# Main.net
KiCad netlist of a schematic drawn in Altium Designer
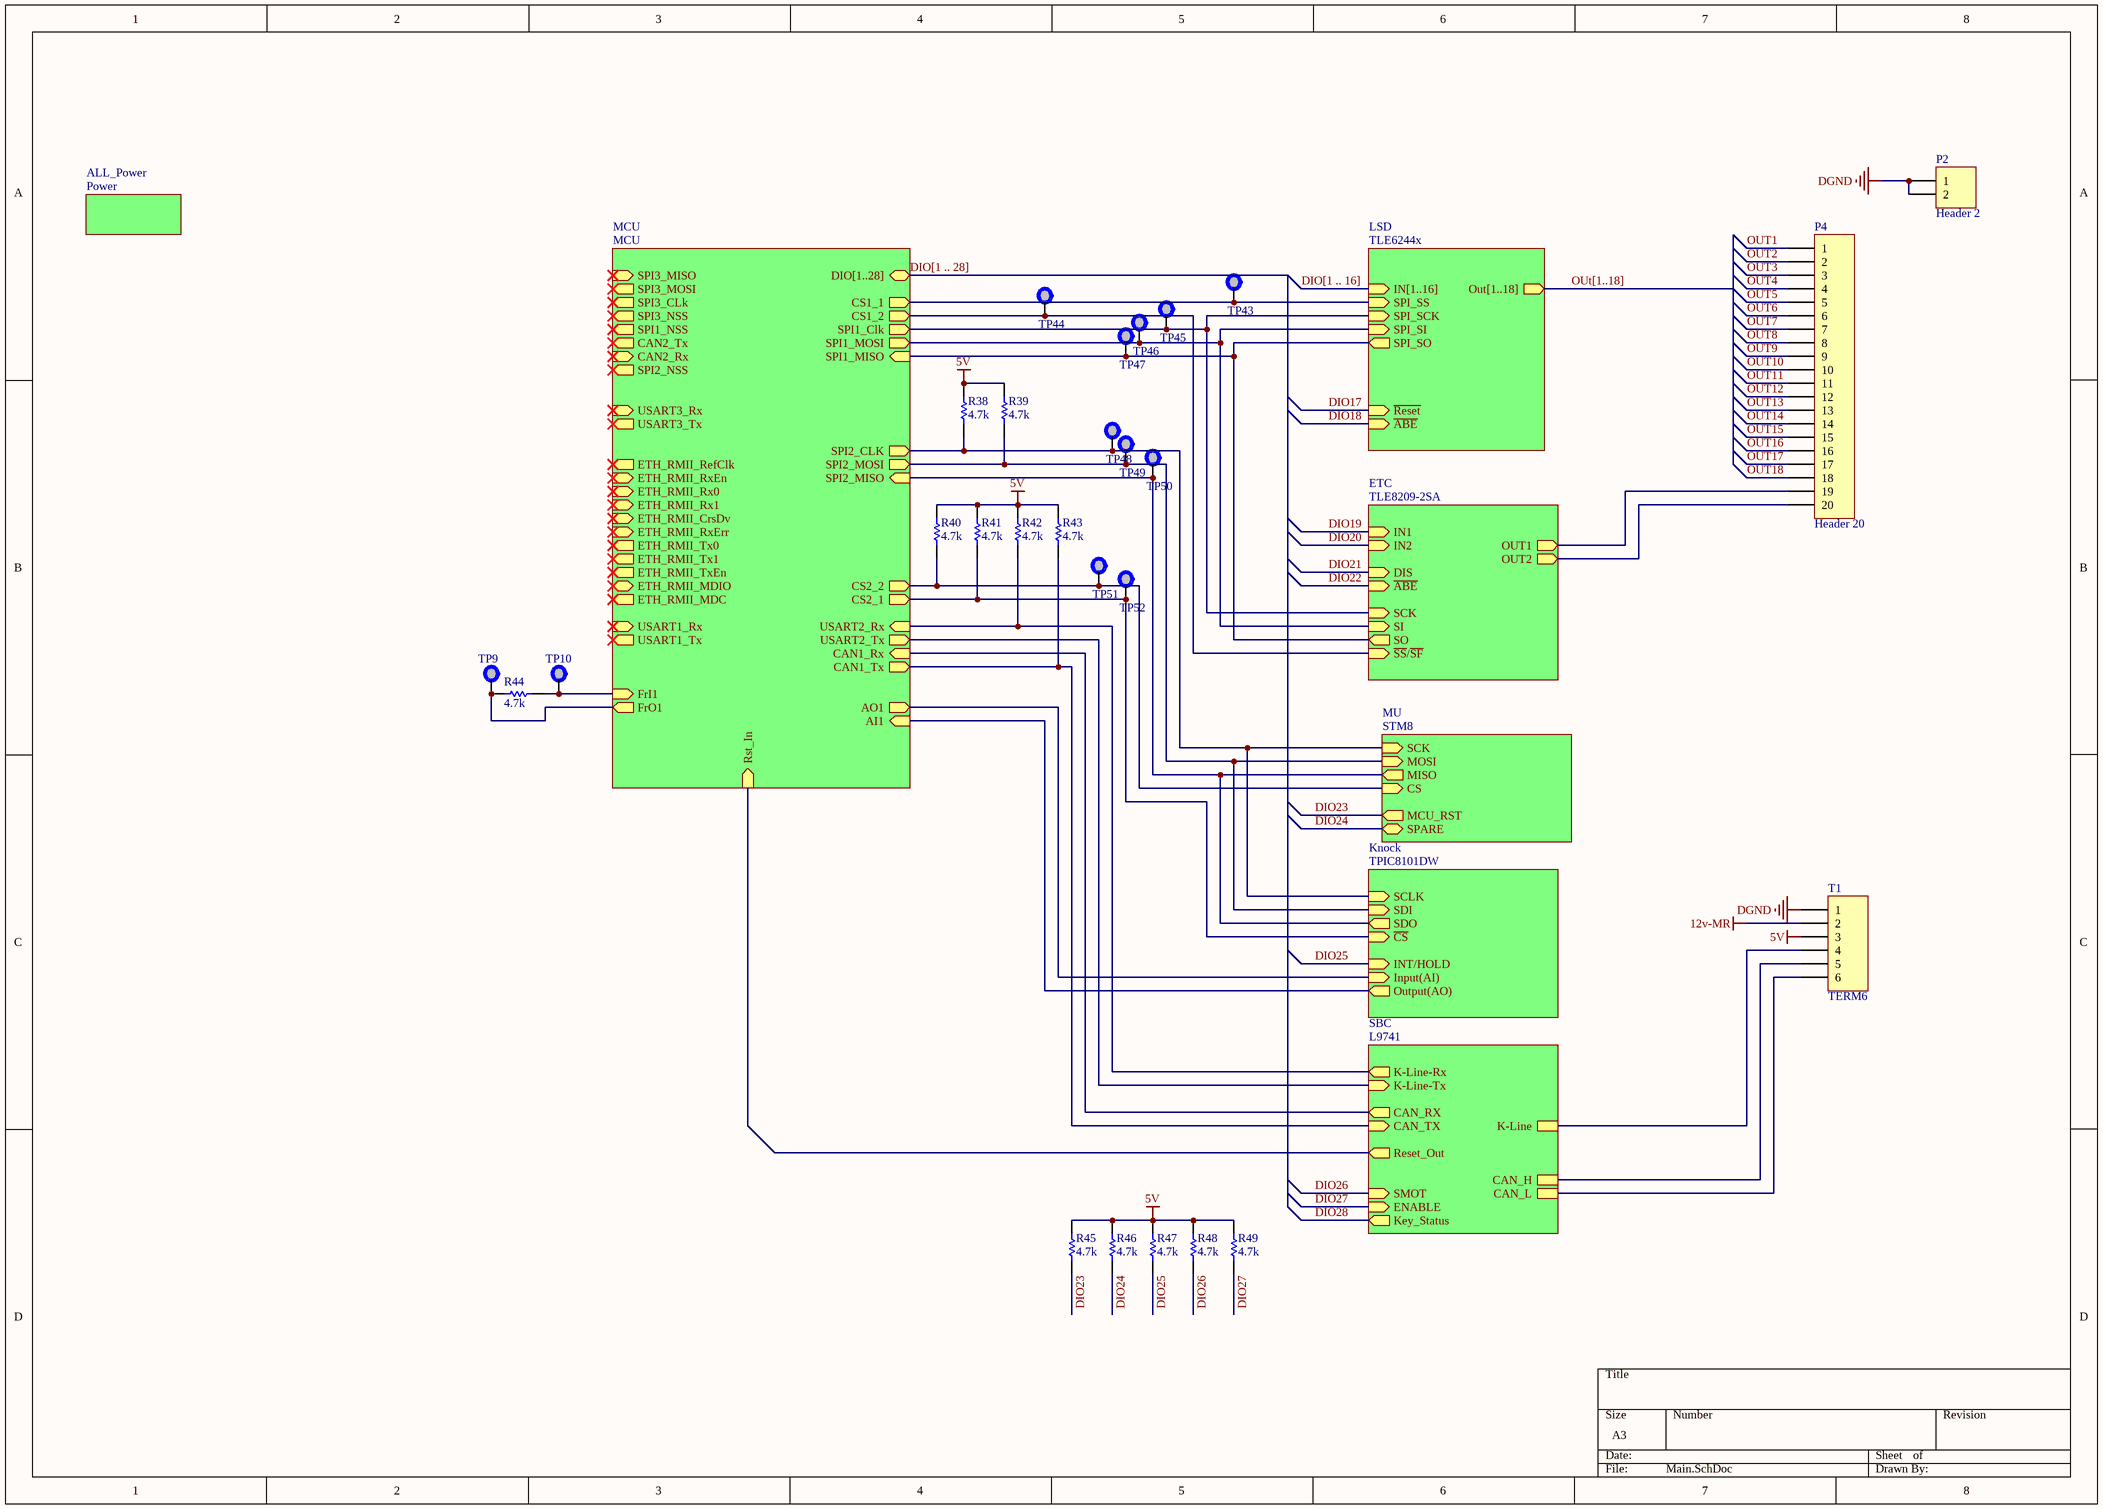
[diagram p0: Main.SchDoc]

(export (version "E")
  (design (tool "Eeschema 10.0.6"))
  (components
    (comp (ref "P2")
      (value "Header 2")
      (footprint "HDR1X2")
      (description "Header, 2-Pin")
      (fields (field (name "PUBLISHER") "Altium Limited"))
      (libsource (lib "Miscellaneous Connectors") (part "Header 2"))
    )
    (comp (ref "P4")
      (value "Header 20")
      (footprint "HDR1X20")
      (description "Header, 20-Pin")
      (fields (field (name "PUBLISHER") "Altium Limited"))
      (libsource (lib "Miscellaneous Connectors") (part "Header 20"))
    )
    (comp (ref "R38")
      (value "4.7k")
      (footprint "0805")
      (description "Resistor")
      (fields (field (name "Comment") "Res1") (field (name "PUBLISHER") "Altium Limited"))
      (libsource (lib "Miscellaneous Devices") (part "Res1"))
    )
    (comp (ref "R39")
      (value "4.7k")
      (footprint "0805")
      (description "Resistor")
      (fields (field (name "Comment") "Res1") (field (name "PUBLISHER") "Altium Limited"))
      (libsource (lib "Miscellaneous Devices") (part "Res1"))
    )
    (comp (ref "R40")
      (value "4.7k")
      (footprint "0805")
      (description "Resistor")
      (fields (field (name "Comment") "Res1") (field (name "PUBLISHER") "Altium Limited"))
      (libsource (lib "Miscellaneous Devices") (part "Res1"))
    )
    (comp (ref "R41")
      (value "4.7k")
      (footprint "0805")
      (description "Resistor")
      (fields (field (name "Comment") "Res1") (field (name "PUBLISHER") "Altium Limited"))
      (libsource (lib "Miscellaneous Devices") (part "Res1"))
    )
    (comp (ref "R42")
      (value "4.7k")
      (footprint "0805")
      (description "Resistor")
      (fields (field (name "Comment") "Res1") (field (name "PUBLISHER") "Altium Limited"))
      (libsource (lib "Miscellaneous Devices") (part "Res1"))
    )
    (comp (ref "R43")
      (value "4.7k")
      (footprint "0805")
      (description "Resistor")
      (fields (field (name "Comment") "Res1") (field (name "PUBLISHER") "Altium Limited"))
      (libsource (lib "Miscellaneous Devices") (part "Res1"))
    )
    (comp (ref "R44")
      (value "4.7k")
      (footprint "0805")
      (description "Resistor")
      (fields (field (name "Comment") "Res1") (field (name "PUBLISHER") "Altium Limited"))
      (libsource (lib "Miscellaneous Devices") (part "Res1"))
    )
    (comp (ref "R45")
      (value "4.7k")
      (footprint "0805")
      (description "Resistor")
      (fields (field (name "Comment") "Res1") (field (name "PUBLISHER") "Altium Limited"))
      (libsource (lib "Miscellaneous Devices") (part "Res1"))
    )
    (comp (ref "R46")
      (value "4.7k")
      (footprint "0805")
      (description "Resistor")
      (fields (field (name "Comment") "Res1") (field (name "PUBLISHER") "Altium Limited"))
      (libsource (lib "Miscellaneous Devices") (part "Res1"))
    )
    (comp (ref "R47")
      (value "4.7k")
      (footprint "0805")
      (description "Resistor")
      (fields (field (name "Comment") "Res1") (field (name "PUBLISHER") "Altium Limited"))
      (libsource (lib "Miscellaneous Devices") (part "Res1"))
    )
    (comp (ref "R48")
      (value "4.7k")
      (footprint "0805")
      (description "Resistor")
      (fields (field (name "Comment") "Res1") (field (name "PUBLISHER") "Altium Limited"))
      (libsource (lib "Miscellaneous Devices") (part "Res1"))
    )
    (comp (ref "R49")
      (value "4.7k")
      (footprint "0805")
      (description "Resistor")
      (fields (field (name "Comment") "Res1") (field (name "PUBLISHER") "Altium Limited"))
      (libsource (lib "Miscellaneous Devices") (part "Res1"))
    )
    (comp (ref "T1")
      (value "TERM6")
      (footprint "TERM6")
      (description "Header, 6-Pin")
      (fields (field (name "PUBLISHER") "Altium Limited"))
      (libsource (lib "Miscellaneous Connectors") (part "MHDR1X6"))
    )
    (comp (ref "TP9") (value "TestPoint") (footprint "TP") (libsource (lib "SchlibV0.1") (part "TestPoint")))
    (comp (ref "TP10") (value "TestPoint") (footprint "TP") (libsource (lib "SchlibV0.1") (part "TestPoint")))
    (comp (ref "TP43") (value "TestPoint") (footprint "TP") (libsource (lib "SchlibV0.1") (part "TestPoint")))
    (comp (ref "TP44") (value "TestPoint") (footprint "TP") (libsource (lib "SchlibV0.1") (part "TestPoint")))
    (comp (ref "TP45") (value "TestPoint") (footprint "TP") (libsource (lib "SchlibV0.1") (part "TestPoint")))
    (comp (ref "TP46") (value "TestPoint") (footprint "TP") (libsource (lib "SchlibV0.1") (part "TestPoint")))
    (comp (ref "TP47") (value "TestPoint") (footprint "TP") (libsource (lib "SchlibV0.1") (part "TestPoint")))
    (comp (ref "TP48") (value "TestPoint") (footprint "TP") (libsource (lib "SchlibV0.1") (part "TestPoint")))
    (comp (ref "TP49") (value "TestPoint") (footprint "TP") (libsource (lib "SchlibV0.1") (part "TestPoint")))
    (comp (ref "TP50") (value "TestPoint") (footprint "TP") (libsource (lib "SchlibV0.1") (part "TestPoint")))
    (comp (ref "TP51") (value "TestPoint") (footprint "TP") (libsource (lib "SchlibV0.1") (part "TestPoint")))
    (comp (ref "TP52") (value "TestPoint") (footprint "TP") (libsource (lib "SchlibV0.1") (part "TestPoint")))
  )
  (nets
    (net (code "22") (name "/CAN1_Tx") (class "Default")
      (node (ref "R43") (pin "1") (pinfunction "1_1") (pintype "passive"))
    )
    (net (code "25") (name "/CAN_H") (class "Default")
      (node (ref "T1") (pin "5") (pinfunction "5_5") (pintype "passive"))
    )
    (net (code "26") (name "/CAN_L") (class "Default")
      (node (ref "T1") (pin "6") (pinfunction "6_6") (pintype "passive"))
    )
    (net (code "28") (name "/CS1_1") (class "Default") (node (ref "TP43") (pin "1") (pintype "passive")))
    (net (code "29") (name "/CS1_2") (class "Default") (node (ref "TP44") (pin "1") (pintype "passive")))
    (net (code "30") (name "/CS2_1") (class "Default")
      (node (ref "R41") (pin "1") (pinfunction "1_1") (pintype "passive"))
      (node (ref "TP52") (pin "1") (pintype "passive"))
    )
    (net (code "31") (name "/CS2_2") (class "Default")
      (node (ref "R40") (pin "2") (pinfunction "2_2") (pintype "passive"))
      (node (ref "TP51") (pin "1") (pintype "passive"))
    )
    (net (code "38") (name "/DIO23") (class "Default")
      (node (ref "R45") (pin "2") (pinfunction "2_2") (pintype "passive"))
    )
    (net (code "39") (name "/DIO24") (class "Default")
      (node (ref "R46") (pin "2") (pinfunction "2_2") (pintype "passive"))
    )
    (net (code "40") (name "/DIO25") (class "Default")
      (node (ref "R47") (pin "2") (pinfunction "2_2") (pintype "passive"))
    )
    (net (code "41") (name "/DIO26") (class "Default")
      (node (ref "R48") (pin "2") (pinfunction "2_2") (pintype "passive"))
    )
    (net (code "42") (name "/DIO27") (class "Default")
      (node (ref "R49") (pin "2") (pinfunction "2_2") (pintype "passive"))
    )
    (net (code "55") (name "/FrI1") (class "Default")
      (node (ref "R44") (pin "2") (pinfunction "2_2") (pintype "passive"))
      (node (ref "TP10") (pin "1") (pintype "passive"))
    )
    (net (code "56") (name "/FrO1") (class "Default")
      (node (ref "R44") (pin "1") (pinfunction "1_1") (pintype "passive"))
      (node (ref "TP9") (pin "1") (pintype "passive"))
    )
    (net (code "57") (name "/K-Line") (class "Default")
      (node (ref "T1") (pin "4") (pinfunction "4_4") (pintype "passive"))
    )
    (net (code "58") (name "/K-Line-Rx") (class "Default")
      (node (ref "R42") (pin "1") (pinfunction "1_1") (pintype "passive"))
    )
    (net (code "59") (name "/MISO") (class "Default") (node (ref "TP50") (pin "1") (pintype "passive")))
    (net (code "60") (name "/OUT1") (class "Default")
      (node (ref "P4") (pin "1") (pinfunction "1_1") (pintype "passive"))
    )
    (net (code "61") (name "/OUT1_1") (class "Default")
      (node (ref "P4") (pin "19") (pinfunction "19_19") (pintype "passive"))
    )
    (net (code "62") (name "/OUT2") (class "Default")
      (node (ref "P4") (pin "2") (pinfunction "2_2") (pintype "passive"))
    )
    (net (code "63") (name "/OUT2_1") (class "Default")
      (node (ref "P4") (pin "20") (pinfunction "20_20") (pintype "passive"))
    )
    (net (code "64") (name "/OUT3") (class "Default")
      (node (ref "P4") (pin "3") (pinfunction "3_3") (pintype "passive"))
    )
    (net (code "65") (name "/OUT4") (class "Default")
      (node (ref "P4") (pin "4") (pinfunction "4_4") (pintype "passive"))
    )
    (net (code "66") (name "/OUT5") (class "Default")
      (node (ref "P4") (pin "5") (pinfunction "5_5") (pintype "passive"))
    )
    (net (code "67") (name "/OUT6") (class "Default")
      (node (ref "P4") (pin "6") (pinfunction "6_6") (pintype "passive"))
    )
    (net (code "68") (name "/OUT7") (class "Default")
      (node (ref "P4") (pin "7") (pinfunction "7_7") (pintype "passive"))
    )
    (net (code "69") (name "/OUT8") (class "Default")
      (node (ref "P4") (pin "8") (pinfunction "8_8") (pintype "passive"))
    )
    (net (code "70") (name "/OUT9") (class "Default")
      (node (ref "P4") (pin "9") (pinfunction "9_9") (pintype "passive"))
    )
    (net (code "71") (name "/OUT10") (class "Default")
      (node (ref "P4") (pin "10") (pinfunction "10_10") (pintype "passive"))
    )
    (net (code "72") (name "/OUT11") (class "Default")
      (node (ref "P4") (pin "11") (pinfunction "11_11") (pintype "passive"))
    )
    (net (code "73") (name "/OUT12") (class "Default")
      (node (ref "P4") (pin "12") (pinfunction "12_12") (pintype "passive"))
    )
    (net (code "74") (name "/OUT13") (class "Default")
      (node (ref "P4") (pin "13") (pinfunction "13_13") (pintype "passive"))
    )
    (net (code "75") (name "/OUT14") (class "Default")
      (node (ref "P4") (pin "14") (pinfunction "14_14") (pintype "passive"))
    )
    (net (code "76") (name "/OUT15") (class "Default")
      (node (ref "P4") (pin "15") (pinfunction "15_15") (pintype "passive"))
    )
    (net (code "77") (name "/OUT16") (class "Default")
      (node (ref "P4") (pin "16") (pinfunction "16_16") (pintype "passive"))
    )
    (net (code "78") (name "/OUT17") (class "Default")
      (node (ref "P4") (pin "17") (pinfunction "17_17") (pintype "passive"))
    )
    (net (code "79") (name "/OUT18") (class "Default")
      (node (ref "P4") (pin "18") (pinfunction "18_18") (pintype "passive"))
    )
    (net (code "83") (name "/SO") (class "Default") (node (ref "TP47") (pin "1") (pintype "passive")))
    (net (code "84") (name "/SPI1_Clk") (class "Default") (node (ref "TP45") (pin "1") (pintype "passive")))
    (net (code "85") (name "/SPI1_MOSI") (class "Default") (node (ref "TP46") (pin "1") (pintype "passive")))
    (net (code "87") (name "/SPI2_CLK") (class "Default")
      (node (ref "R38") (pin "1") (pinfunction "1_1") (pintype "passive"))
      (node (ref "TP48") (pin "1") (pintype "passive"))
    )
    (net (code "88") (name "/SPI2_MOSI") (class "Default")
      (node (ref "R39") (pin "1") (pinfunction "1_1") (pintype "passive"))
      (node (ref "TP49") (pin "1") (pintype "passive"))
    )
    (net (code "101") (name "5V") (class "Default")
      (node (ref "R38") (pin "2") (pinfunction "2_2") (pintype "passive"))
      (node (ref "R39") (pin "2") (pinfunction "2_2") (pintype "passive"))
      (node (ref "R40") (pin "1") (pinfunction "1_1") (pintype "passive"))
      (node (ref "R41") (pin "2") (pinfunction "2_2") (pintype "passive"))
      (node (ref "R42") (pin "2") (pinfunction "2_2") (pintype "passive"))
      (node (ref "R43") (pin "2") (pinfunction "2_2") (pintype "passive"))
      (node (ref "R45") (pin "1") (pinfunction "1_1") (pintype "passive"))
      (node (ref "R46") (pin "1") (pinfunction "1_1") (pintype "passive"))
      (node (ref "R47") (pin "1") (pinfunction "1_1") (pintype "passive"))
      (node (ref "R48") (pin "1") (pinfunction "1_1") (pintype "passive"))
      (node (ref "R49") (pin "1") (pinfunction "1_1") (pintype "passive"))
      (node (ref "T1") (pin "3") (pinfunction "3_3") (pintype "passive"))
    )
    (net (code "102") (name "12v-MR") (class "Default")
      (node (ref "T1") (pin "2") (pinfunction "2_2") (pintype "passive"))
    )
    (net (code "103") (name "DGND") (class "Default")
      (node (ref "P2") (pin "1") (pinfunction "1_1") (pintype "passive"))
      (node (ref "P2") (pin "2") (pinfunction "2_2") (pintype "passive"))
      (node (ref "T1") (pin "1") (pinfunction "1_1") (pintype "passive"))
    )
  )
)
